# MainBoard_V1_2.net
KiCad netlist of a schematic drawn in EAGLE
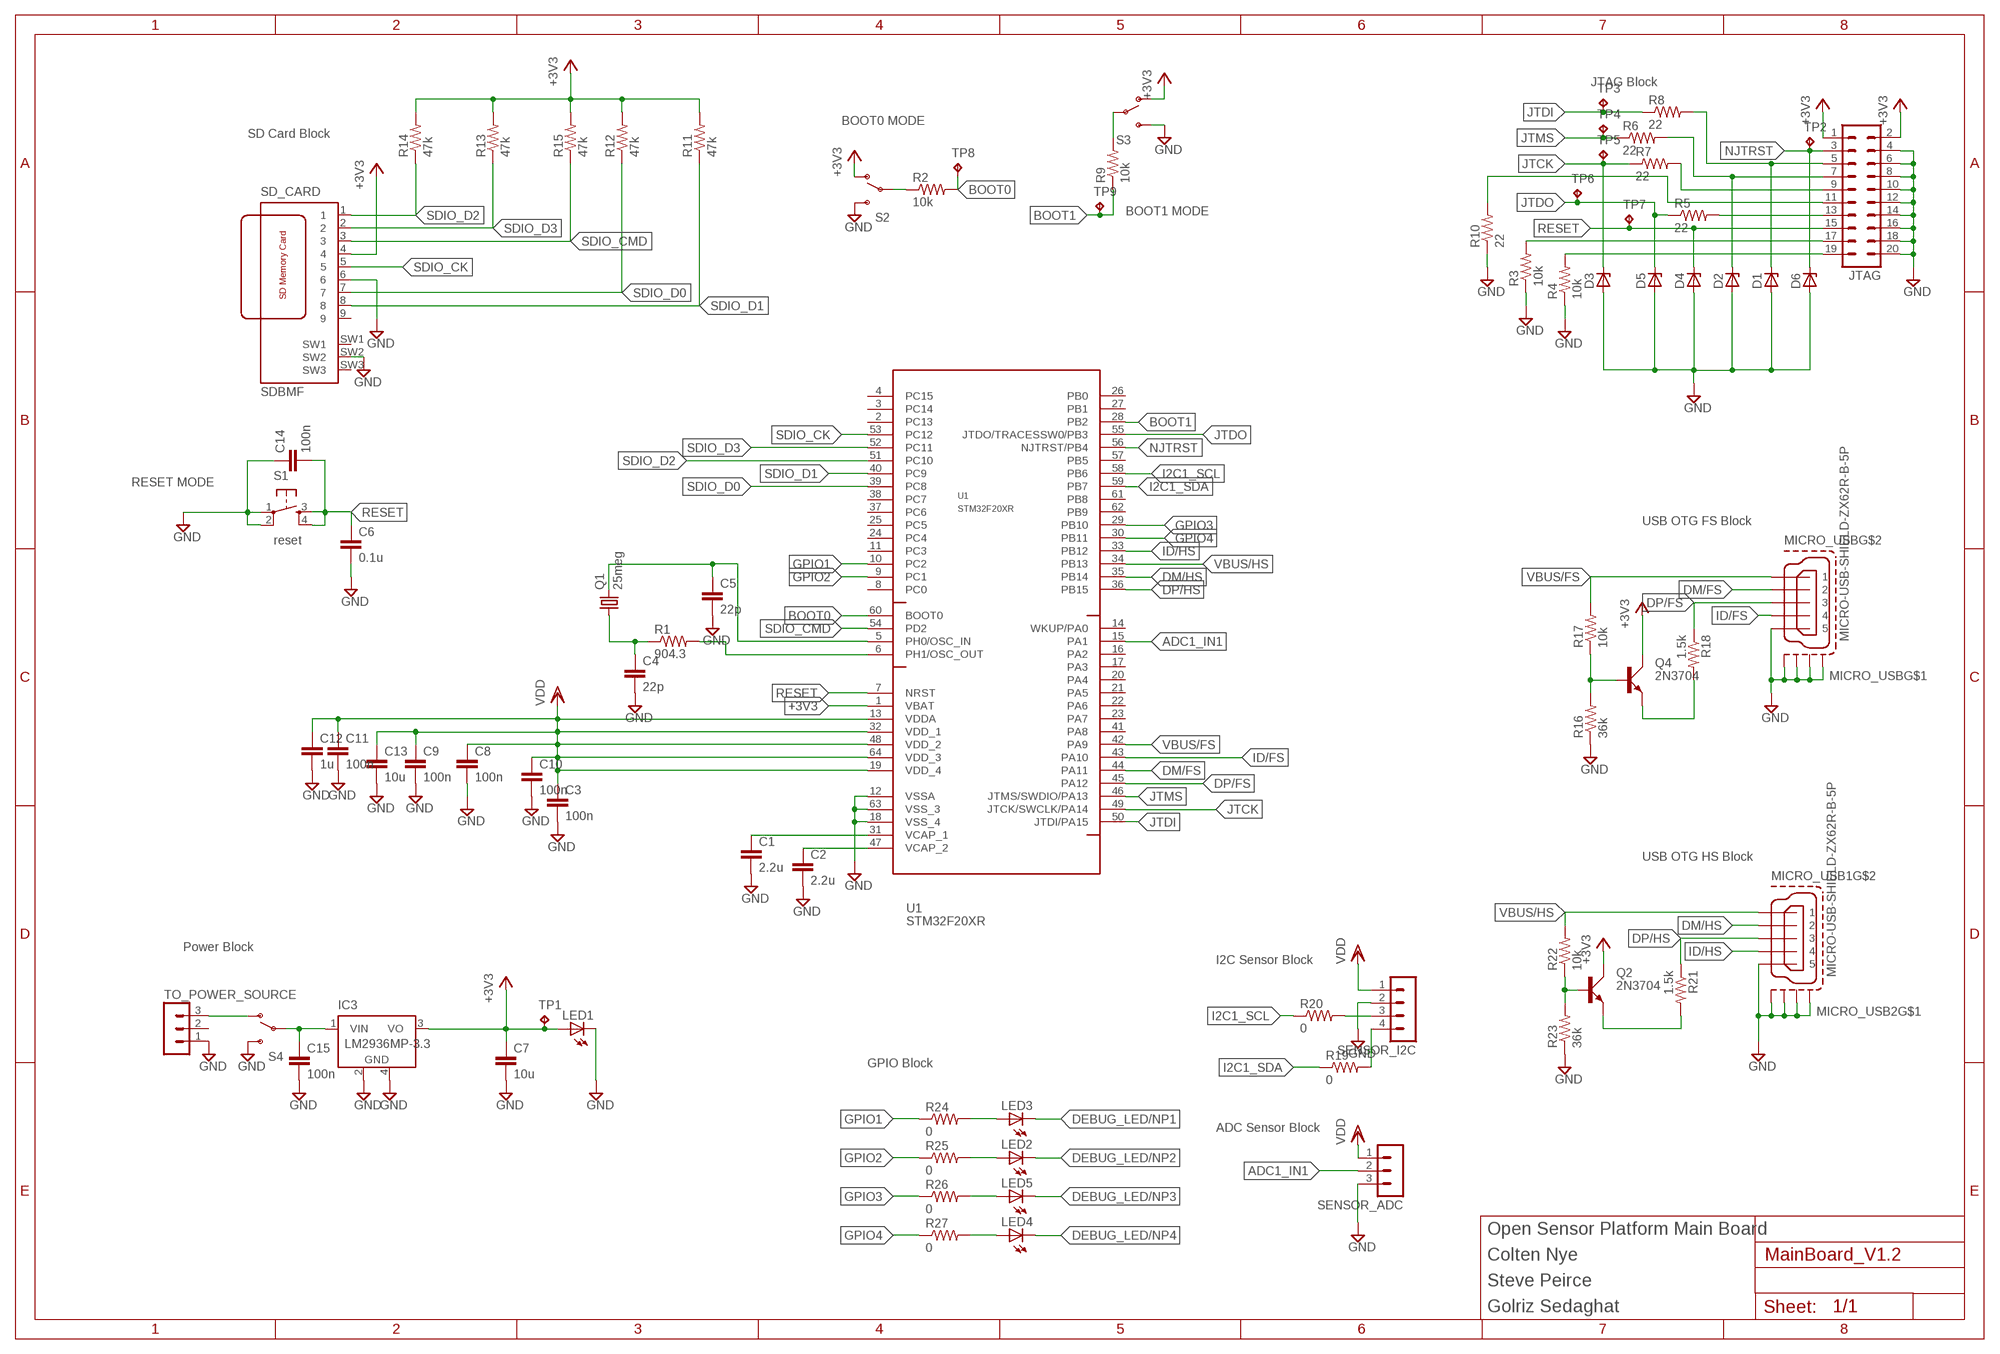
[diagram p0: schematic, sheet 1]

(export (version "E")
  (design (tool "Eeschema 10.0.6"))
  (components
    (comp (ref "C1")
      (value "2.2u")
      (footprint "eagle-import:C0805")
      (libsource (lib "eagle-import") (part "C-EUC0805"))
    )
    (comp (ref "C2")
      (value "2.2u")
      (footprint "eagle-import:C0805")
      (libsource (lib "eagle-import") (part "C-EUC0805"))
    )
    (comp (ref "C3")
      (value "100n")
      (footprint "eagle-import:C0805")
      (libsource (lib "eagle-import") (part "C-EUC0805"))
    )
    (comp (ref "C4")
      (value "22p")
      (footprint "eagle-import:C0805")
      (libsource (lib "eagle-import") (part "C-EUC0805"))
    )
    (comp (ref "C5")
      (value "22p")
      (footprint "eagle-import:C0805")
      (libsource (lib "eagle-import") (part "C-EUC0805"))
    )
    (comp (ref "C6")
      (value "0.1u")
      (footprint "eagle-import:C0805")
      (libsource (lib "eagle-import") (part "C-EUC0805"))
    )
    (comp (ref "C7")
      (value "10u")
      (footprint "eagle-import:C0805")
      (libsource (lib "eagle-import") (part "C-EUC0805"))
    )
    (comp (ref "C8")
      (value "100n")
      (footprint "eagle-import:C0805")
      (libsource (lib "eagle-import") (part "C-EUC0805"))
    )
    (comp (ref "C9")
      (value "100n")
      (footprint "eagle-import:C0805")
      (libsource (lib "eagle-import") (part "C-EUC0805"))
    )
    (comp (ref "C10")
      (value "100n")
      (footprint "eagle-import:C0805")
      (libsource (lib "eagle-import") (part "C-EUC0805"))
    )
    (comp (ref "C11")
      (value "100n")
      (footprint "eagle-import:C0805")
      (libsource (lib "eagle-import") (part "C-EUC0805"))
    )
    (comp (ref "C12")
      (value "1u")
      (footprint "eagle-import:C0805")
      (libsource (lib "eagle-import") (part "C-EUC0805"))
    )
    (comp (ref "C13")
      (value "10u")
      (footprint "eagle-import:C0805")
      (libsource (lib "eagle-import") (part "C-EUC0805"))
    )
    (comp (ref "C14")
      (value "100n")
      (footprint "eagle-import:C0805")
      (libsource (lib "eagle-import") (part "C-EUC0805"))
    )
    (comp (ref "C15")
      (value "100n")
      (footprint "eagle-import:C0805")
      (libsource (lib "eagle-import") (part "C-EUC0805"))
    )
    (comp (ref "D1")
      (value "ZENER-DIODEZD-5")
      (footprint "eagle-import:ZDIO-5")
      (libsource (lib "eagle-import") (part "ZENER-DIODEZD-5"))
    )
    (comp (ref "D2")
      (value "ZENER-DIODEZD-5")
      (footprint "eagle-import:ZDIO-5")
      (libsource (lib "eagle-import") (part "ZENER-DIODEZD-5"))
    )
    (comp (ref "D3")
      (value "ZENER-DIODEZD-5")
      (footprint "eagle-import:ZDIO-5")
      (libsource (lib "eagle-import") (part "ZENER-DIODEZD-5"))
    )
    (comp (ref "D4")
      (value "ZENER-DIODEZD-5")
      (footprint "eagle-import:ZDIO-5")
      (libsource (lib "eagle-import") (part "ZENER-DIODEZD-5"))
    )
    (comp (ref "D5")
      (value "ZENER-DIODEZD-5")
      (footprint "eagle-import:ZDIO-5")
      (libsource (lib "eagle-import") (part "ZENER-DIODEZD-5"))
    )
    (comp (ref "D6")
      (value "ZENER-DIODEZD-5")
      (footprint "eagle-import:ZDIO-5")
      (libsource (lib "eagle-import") (part "ZENER-DIODEZD-5"))
    )
    (comp (ref "IC3")
      (value "LM2936MP-3.3")
      (footprint "eagle-import:SOT223")
      (fields (field (name "MF") "NATIONAL SEMICONDUCTOR") (field (name "MPN") "LM2936MP-3.3/NOPB"))
      (libsource (lib "eagle-import") (part "LM2936MP?-3.3"))
    )
    (comp (ref "JTAG")
      (value "MA10-2")
      (footprint "eagle-import:MA10-2")
      (libsource (lib "eagle-import") (part "MA10-2"))
    )
    (comp (ref "LED1")
      (value "LEDSML0805")
      (footprint "eagle-import:SML0805")
      (libsource (lib "eagle-import") (part "LEDSML0805"))
    )
    (comp (ref "LED2")
      (value "LEDSML0805")
      (footprint "eagle-import:SML0805")
      (libsource (lib "eagle-import") (part "LEDSML0805"))
    )
    (comp (ref "LED3")
      (value "LEDSML0805")
      (footprint "eagle-import:SML0805")
      (libsource (lib "eagle-import") (part "LEDSML0805"))
    )
    (comp (ref "LED4")
      (value "LEDSML0805")
      (footprint "eagle-import:SML0805")
      (libsource (lib "eagle-import") (part "LEDSML0805"))
    )
    (comp (ref "LED5")
      (value "LEDSML0805")
      (footprint "eagle-import:SML0805")
      (libsource (lib "eagle-import") (part "LEDSML0805"))
    )
    (comp (ref "MICRO_USB")
      (value "MICRO-USB-SHIELD-ZX62R-B-5P")
      (footprint "eagle-import:ZX62R-B-5P")
      (libsource (lib "eagle-import") (part "MICRO-USB-SHIELD-ZX62R-B-5P"))
    )
    (comp (ref "MICRO_USB1")
      (value "MICRO-USB-SHIELD-ZX62R-B-5P")
      (footprint "eagle-import:ZX62R-B-5P")
      (libsource (lib "eagle-import") (part "MICRO-USB-SHIELD-ZX62R-B-5P"))
    )
    (comp (ref "MICRO_USB2")
      (value "MICRO-USB-SHIELD-ZX62R-B-5P")
      (footprint "eagle-import:ZX62R-B-5P")
      (libsource (lib "eagle-import") (part "MICRO-USB-SHIELD-ZX62R-B-5P"))
    )
    (comp (ref "Q1")
      (value "25meg")
      (footprint "eagle-import:HC49_S")
      (libsource (lib "eagle-import") (part "CRYSTALHC49S"))
    )
    (comp (ref "Q2")
      (value "2N3704")
      (footprint "eagle-import:TO92C")
      (libsource (lib "eagle-import") (part "2N3704"))
    )
    (comp (ref "Q4")
      (value "2N3704")
      (footprint "eagle-import:TO92C")
      (libsource (lib "eagle-import") (part "2N3704"))
    )
    (comp (ref "R1")
      (value "904.3")
      (footprint "eagle-import:R0805")
      (libsource (lib "eagle-import") (part "R-US_R0805"))
    )
    (comp (ref "R2")
      (value "10k")
      (footprint "eagle-import:R0805")
      (libsource (lib "eagle-import") (part "R-US_R0805"))
    )
    (comp (ref "R3")
      (value "10k")
      (footprint "eagle-import:R0805")
      (libsource (lib "eagle-import") (part "R-US_R0805"))
    )
    (comp (ref "R4")
      (value "10k")
      (footprint "eagle-import:R0805")
      (libsource (lib "eagle-import") (part "R-US_R0805"))
    )
    (comp (ref "R5")
      (value "22")
      (footprint "eagle-import:R0805")
      (libsource (lib "eagle-import") (part "R-US_R0805"))
    )
    (comp (ref "R6")
      (value "22")
      (footprint "eagle-import:R0805")
      (libsource (lib "eagle-import") (part "R-US_R0805"))
    )
    (comp (ref "R7")
      (value "22")
      (footprint "eagle-import:R0805")
      (libsource (lib "eagle-import") (part "R-US_R0805"))
    )
    (comp (ref "R8")
      (value "22")
      (footprint "eagle-import:R0805")
      (libsource (lib "eagle-import") (part "R-US_R0805"))
    )
    (comp (ref "R9")
      (value "10k")
      (footprint "eagle-import:R0805")
      (libsource (lib "eagle-import") (part "R-US_R0805"))
    )
    (comp (ref "R10")
      (value "22")
      (footprint "eagle-import:R0805")
      (libsource (lib "eagle-import") (part "R-US_R0805"))
    )
    (comp (ref "R11")
      (value "47k")
      (footprint "eagle-import:R0805")
      (libsource (lib "eagle-import") (part "R-US_R0805"))
    )
    (comp (ref "R12")
      (value "47k")
      (footprint "eagle-import:R0805")
      (libsource (lib "eagle-import") (part "R-US_R0805"))
    )
    (comp (ref "R13")
      (value "47k")
      (footprint "eagle-import:R0805")
      (libsource (lib "eagle-import") (part "R-US_R0805"))
    )
    (comp (ref "R14")
      (value "47k")
      (footprint "eagle-import:R0805")
      (libsource (lib "eagle-import") (part "R-US_R0805"))
    )
    (comp (ref "R15")
      (value "47k")
      (footprint "eagle-import:R0805")
      (libsource (lib "eagle-import") (part "R-US_R0805"))
    )
    (comp (ref "R16")
      (value "36k")
      (footprint "eagle-import:R0805")
      (libsource (lib "eagle-import") (part "R-US_R0805"))
    )
    (comp (ref "R17")
      (value "10k")
      (footprint "eagle-import:R0805")
      (libsource (lib "eagle-import") (part "R-US_R0805"))
    )
    (comp (ref "R18")
      (value "1.5k")
      (footprint "eagle-import:R0805")
      (libsource (lib "eagle-import") (part "R-US_R0805"))
    )
    (comp (ref "R19")
      (value "0")
      (footprint "eagle-import:R0805")
      (libsource (lib "eagle-import") (part "R-US_R0805"))
    )
    (comp (ref "R20")
      (value "0")
      (footprint "eagle-import:R0805")
      (libsource (lib "eagle-import") (part "R-US_R0805"))
    )
    (comp (ref "R21")
      (value "1.5k")
      (footprint "eagle-import:R0805")
      (libsource (lib "eagle-import") (part "R-US_R0805"))
    )
    (comp (ref "R22")
      (value "10k")
      (footprint "eagle-import:R0805")
      (libsource (lib "eagle-import") (part "R-US_R0805"))
    )
    (comp (ref "R23")
      (value "36k")
      (footprint "eagle-import:R0805")
      (libsource (lib "eagle-import") (part "R-US_R0805"))
    )
    (comp (ref "R24")
      (value "0")
      (footprint "eagle-import:R0805")
      (libsource (lib "eagle-import") (part "R-US_R0805"))
    )
    (comp (ref "R25")
      (value "0")
      (footprint "eagle-import:R0805")
      (libsource (lib "eagle-import") (part "R-US_R0805"))
    )
    (comp (ref "R26")
      (value "0")
      (footprint "eagle-import:R0805")
      (libsource (lib "eagle-import") (part "R-US_R0805"))
    )
    (comp (ref "R27")
      (value "0")
      (footprint "eagle-import:R0805")
      (libsource (lib "eagle-import") (part "R-US_R0805"))
    )
    (comp (ref "S1")
      (value "reset")
      (footprint "eagle-import:TACTILE-SWITCH-SMD")
      (libsource (lib "eagle-import") (part "TAC_SWITCHSMD"))
    )
    (comp (ref "S2")
      (value "SWITCH-SPDT-SMD-A")
      (footprint "eagle-import:SWITCH-SPST-SMD-A")
      (libsource (lib "eagle-import") (part "SWITCH-SPDT-SMD-A"))
    )
    (comp (ref "S3")
      (value "SWITCH-SPDT-SMD-A")
      (footprint "eagle-import:SWITCH-SPST-SMD-A")
      (libsource (lib "eagle-import") (part "SWITCH-SPDT-SMD-A"))
    )
    (comp (ref "S4")
      (value "SWITCH-SPDT-SMD-A")
      (footprint "eagle-import:SWITCH-SPST-SMD-A")
      (libsource (lib "eagle-import") (part "SWITCH-SPDT-SMD-A"))
    )
    (comp (ref "SD_CARD")
      (value "SDBMF")
      (footprint "eagle-import:SDBMF-009XXBXX2")
      (libsource (lib "eagle-import") (part "SDBMF"))
    )
    (comp (ref "SENSOR_ADC")
      (value "MA03-1")
      (footprint "eagle-import:MA03-1")
      (libsource (lib "eagle-import") (part "MA03-1"))
    )
    (comp (ref "SENSOR_I2C")
      (value "MA04-1")
      (footprint "eagle-import:MA04-1")
      (libsource (lib "eagle-import") (part "MA04-1"))
    )
    (comp (ref "TO_POWER_SOURCE")
      (value "MA03-1")
      (footprint "eagle-import:MA03-1")
      (libsource (lib "eagle-import") (part "MA03-1"))
    )
    (comp (ref "TP1")
      (value "TPB1,27")
      (footprint "eagle-import:B1,27")
      (libsource (lib "eagle-import") (part "TPB1,27"))
    )
    (comp (ref "TP2")
      (value "TPB1,27")
      (footprint "eagle-import:B1,27")
      (libsource (lib "eagle-import") (part "TPB1,27"))
    )
    (comp (ref "TP3")
      (value "TPB1,27")
      (footprint "eagle-import:B1,27")
      (libsource (lib "eagle-import") (part "TPB1,27"))
    )
    (comp (ref "TP4")
      (value "TPB1,27")
      (footprint "eagle-import:B1,27")
      (libsource (lib "eagle-import") (part "TPB1,27"))
    )
    (comp (ref "TP5")
      (value "TPB1,27")
      (footprint "eagle-import:B1,27")
      (libsource (lib "eagle-import") (part "TPB1,27"))
    )
    (comp (ref "TP6")
      (value "TPB1,27")
      (footprint "eagle-import:B1,27")
      (libsource (lib "eagle-import") (part "TPB1,27"))
    )
    (comp (ref "TP7")
      (value "TPB1,27")
      (footprint "eagle-import:B1,27")
      (libsource (lib "eagle-import") (part "TPB1,27"))
    )
    (comp (ref "TP8")
      (value "TPB1,27")
      (footprint "eagle-import:B1,27")
      (libsource (lib "eagle-import") (part "TPB1,27"))
    )
    (comp (ref "TP9")
      (value "TPB1,27")
      (footprint "eagle-import:B1,27")
      (libsource (lib "eagle-import") (part "TPB1,27"))
    )
    (comp (ref "U1")
      (value "STM32F20XR")
      (footprint "eagle-import:LQFP64")
      (libsource (lib "eagle-import") (part "STM32F20XR"))
    )
  )
  (nets
    (net (code "1") (name "+3V3") (class "Default")
      (node (ref "C7") (pin "1") (pinfunction "1_1") (pintype "passive"))
      (node (ref "IC3") (pin "3") (pinfunction "VO_3") (pintype "passive"))
      (node (ref "JTAG") (pin "1") (pinfunction "1_1") (pintype "passive"))
      (node (ref "JTAG") (pin "2") (pinfunction "2_2") (pintype "passive"))
      (node (ref "LED1") (pin "A") (pinfunction "A_A") (pintype "passive"))
      (node (ref "Q2") (pin "C") (pinfunction "C_C") (pintype "passive"))
      (node (ref "Q4") (pin "C") (pinfunction "C_C") (pintype "passive"))
      (node (ref "R11") (pin "2") (pinfunction "2_2") (pintype "passive"))
      (node (ref "R12") (pin "2") (pinfunction "2_2") (pintype "passive"))
      (node (ref "R13") (pin "2") (pinfunction "2_2") (pintype "passive"))
      (node (ref "R14") (pin "2") (pinfunction "2_2") (pintype "passive"))
      (node (ref "R15") (pin "2") (pinfunction "2_2") (pintype "passive"))
      (node (ref "S2") (pin "1") (pinfunction "O_1") (pintype "passive"))
      (node (ref "S3") (pin "1") (pinfunction "O_1") (pintype "passive"))
      (node (ref "SD_CARD") (pin "4") (pinfunction "4_4") (pintype "passive"))
      (node (ref "TP1") (pin "TP") (pinfunction "TP_TP") (pintype "input"))
      (node (ref "U1") (pin "1") (pinfunction "VBAT_1") (pintype "power_in"))
    )
    (net (code "2") (name "ADC1_IN1") (class "Default")
      (node (ref "SENSOR_ADC") (pin "2") (pinfunction "2_2") (pintype "passive"))
      (node (ref "U1") (pin "15") (pinfunction "PA1_15") (pintype "bidirectional"))
    )
    (net (code "3") (name "BOOT0") (class "Default")
      (node (ref "R2") (pin "2") (pinfunction "2_2") (pintype "passive"))
      (node (ref "TP8") (pin "TP") (pinfunction "TP_TP") (pintype "input"))
      (node (ref "U1") (pin "60") (pinfunction "BOOT0_60") (pintype "bidirectional"))
    )
    (net (code "4") (name "BOOT1") (class "Default")
      (node (ref "R9") (pin "1") (pinfunction "1_1") (pintype "passive"))
      (node (ref "TP9") (pin "TP") (pinfunction "TP_TP") (pintype "input"))
      (node (ref "U1") (pin "28") (pinfunction "PB2_28") (pintype "bidirectional"))
    )
    (net (code "5") (name "DEBUG_LED{slash}NP1") (class "Default")
      (node (ref "LED3") (pin "C") (pinfunction "C_C") (pintype "passive"))
    )
    (net (code "6") (name "DEBUG_LED{slash}NP2") (class "Default")
      (node (ref "LED2") (pin "C") (pinfunction "C_C") (pintype "passive"))
    )
    (net (code "7") (name "DEBUG_LED{slash}NP3") (class "Default")
      (node (ref "LED5") (pin "C") (pinfunction "C_C") (pintype "passive"))
    )
    (net (code "8") (name "DEBUG_LED{slash}NP4") (class "Default")
      (node (ref "LED4") (pin "C") (pinfunction "C_C") (pintype "passive"))
    )
    (net (code "9") (name "DM{slash}FS") (class "Default")
      (node (ref "MICRO_USB") (pin "2") (pinfunction "2_2") (pintype "input"))
      (node (ref "U1") (pin "44") (pinfunction "PA11_44") (pintype "bidirectional"))
    )
    (net (code "10") (name "DM{slash}HS") (class "Default")
      (node (ref "MICRO_USB1") (pin "2") (pinfunction "2_2") (pintype "input"))
      (node (ref "U1") (pin "35") (pinfunction "PB14_35") (pintype "bidirectional"))
    )
    (net (code "11") (name "DP{slash}FS") (class "Default")
      (node (ref "MICRO_USB") (pin "3") (pinfunction "3_3") (pintype "input"))
      (node (ref "R18") (pin "1") (pinfunction "1_1") (pintype "passive"))
      (node (ref "U1") (pin "45") (pinfunction "PA12_45") (pintype "bidirectional"))
    )
    (net (code "12") (name "DP{slash}HS") (class "Default")
      (node (ref "MICRO_USB1") (pin "3") (pinfunction "3_3") (pintype "input"))
      (node (ref "R21") (pin "1") (pinfunction "1_1") (pintype "passive"))
      (node (ref "U1") (pin "36") (pinfunction "PB15_36") (pintype "bidirectional"))
    )
    (net (code "13") (name "GND") (class "Default")
      (node (ref "C1") (pin "2") (pinfunction "2_2") (pintype "passive"))
      (node (ref "C10") (pin "2") (pinfunction "2_2") (pintype "passive"))
      (node (ref "C11") (pin "2") (pinfunction "2_2") (pintype "passive"))
      (node (ref "C12") (pin "2") (pinfunction "2_2") (pintype "passive"))
      (node (ref "C13") (pin "2") (pinfunction "2_2") (pintype "passive"))
      (node (ref "C14") (pin "1") (pinfunction "1_1") (pintype "passive"))
      (node (ref "C15") (pin "2") (pinfunction "2_2") (pintype "passive"))
      (node (ref "C2") (pin "2") (pinfunction "2_2") (pintype "passive"))
      (node (ref "C3") (pin "2") (pinfunction "2_2") (pintype "passive"))
      (node (ref "C4") (pin "2") (pinfunction "2_2") (pintype "passive"))
      (node (ref "C5") (pin "2") (pinfunction "2_2") (pintype "passive"))
      (node (ref "C6") (pin "2") (pinfunction "2_2") (pintype "passive"))
      (node (ref "C7") (pin "2") (pinfunction "2_2") (pintype "passive"))
      (node (ref "C8") (pin "2") (pinfunction "2_2") (pintype "passive"))
      (node (ref "C9") (pin "2") (pinfunction "2_2") (pintype "passive"))
      (node (ref "D1") (pin "A") (pinfunction "A_A") (pintype "passive"))
      (node (ref "D2") (pin "A") (pinfunction "A_A") (pintype "passive"))
      (node (ref "D3") (pin "A") (pinfunction "A_A") (pintype "passive"))
      (node (ref "D4") (pin "A") (pinfunction "A_A") (pintype "passive"))
      (node (ref "D5") (pin "A") (pinfunction "A_A") (pintype "passive"))
      (node (ref "D6") (pin "A") (pinfunction "A_A") (pintype "passive"))
      (node (ref "IC3") (pin "2") (pinfunction "GND_2") (pintype "passive"))
      (node (ref "IC3") (pin "4") (pinfunction "GND_4") (pintype "passive"))
      (node (ref "JTAG") (pin "10") (pinfunction "10_10") (pintype "passive"))
      (node (ref "JTAG") (pin "12") (pinfunction "12_12") (pintype "passive"))
      (node (ref "JTAG") (pin "14") (pinfunction "14_14") (pintype "passive"))
      (node (ref "JTAG") (pin "16") (pinfunction "16_16") (pintype "passive"))
      (node (ref "JTAG") (pin "18") (pinfunction "18_18") (pintype "passive"))
      (node (ref "JTAG") (pin "20") (pinfunction "20_20") (pintype "passive"))
      (node (ref "JTAG") (pin "4") (pinfunction "4_4") (pintype "passive"))
      (node (ref "JTAG") (pin "6") (pinfunction "6_6") (pintype "passive"))
      (node (ref "JTAG") (pin "8") (pinfunction "8_8") (pintype "passive"))
      (node (ref "LED1") (pin "C") (pinfunction "C_C") (pintype "passive"))
      (node (ref "MICRO_USB") (pin "5") (pinfunction "5_5") (pintype "input"))
      (node (ref "MICRO_USB") (pin "M1") (pinfunction "S1_M1") (pintype "passive"))
      (node (ref "MICRO_USB") (pin "M2") (pinfunction "S2_M2") (pintype "passive"))
      (node (ref "MICRO_USB") (pin "M3") (pinfunction "S3_M3") (pintype "passive"))
      (node (ref "MICRO_USB") (pin "M4") (pinfunction "S4_M4") (pintype "passive"))
      (node (ref "MICRO_USB1") (pin "5") (pinfunction "5_5") (pintype "input"))
      (node (ref "MICRO_USB2") (pin "M1") (pinfunction "S1_M1") (pintype "passive"))
      (node (ref "MICRO_USB2") (pin "M2") (pinfunction "S2_M2") (pintype "passive"))
      (node (ref "MICRO_USB2") (pin "M3") (pinfunction "S3_M3") (pintype "passive"))
      (node (ref "MICRO_USB2") (pin "M4") (pinfunction "S4_M4") (pintype "passive"))
      (node (ref "R10") (pin "1") (pinfunction "1_1") (pintype "passive"))
      (node (ref "R16") (pin "1") (pinfunction "1_1") (pintype "passive"))
      (node (ref "R23") (pin "1") (pinfunction "1_1") (pintype "passive"))
      (node (ref "R3") (pin "1") (pinfunction "1_1") (pintype "passive"))
      (node (ref "R4") (pin "1") (pinfunction "1_1") (pintype "passive"))
      (node (ref "S1") (pin "1") (pinfunction "1_1") (pintype "passive"))
      (node (ref "S1") (pin "2") (pinfunction "2_2") (pintype "passive"))
      (node (ref "S2") (pin "3") (pinfunction "S_3") (pintype "passive"))
      (node (ref "S3") (pin "3") (pinfunction "S_3") (pintype "passive"))
      (node (ref "S4") (pin "3") (pinfunction "S_3") (pintype "passive"))
      (node (ref "SD_CARD") (pin "6") (pinfunction "6_6") (pintype "passive"))
      (node (ref "SD_CARD") (pin "SW2") (pinfunction "SW2_SW2") (pintype "passive"))
      (node (ref "SENSOR_ADC") (pin "3") (pinfunction "3_3") (pintype "passive"))
      (node (ref "SENSOR_I2C") (pin "2") (pinfunction "2_2") (pintype "passive"))
      (node (ref "TO_POWER_SOURCE") (pin "1") (pinfunction "1_1") (pintype "passive"))
      (node (ref "U1") (pin "12") (pinfunction "VSSA_12") (pintype "power_in"))
      (node (ref "U1") (pin "18") (pinfunction "VSS_4_18") (pintype "power_in"))
      (node (ref "U1") (pin "63") (pinfunction "VSS_3_63") (pintype "power_in"))
    )
    (net (code "14") (name "GPIO1") (class "Default")
      (node (ref "R24") (pin "1") (pinfunction "1_1") (pintype "passive"))
      (node (ref "U1") (pin "10") (pinfunction "PC2_10") (pintype "bidirectional"))
    )
    (net (code "15") (name "GPIO2") (class "Default")
      (node (ref "R25") (pin "1") (pinfunction "1_1") (pintype "passive"))
      (node (ref "U1") (pin "9") (pinfunction "PC1_9") (pintype "bidirectional"))
    )
    (net (code "16") (name "GPIO3") (class "Default")
      (node (ref "R26") (pin "1") (pinfunction "1_1") (pintype "passive"))
      (node (ref "U1") (pin "29") (pinfunction "PB10_29") (pintype "bidirectional"))
    )
    (net (code "17") (name "GPIO4") (class "Default")
      (node (ref "R27") (pin "1") (pinfunction "1_1") (pintype "passive"))
      (node (ref "U1") (pin "30") (pinfunction "PB11_30") (pintype "bidirectional"))
    )
    (net (code "18") (name "I2C1_SCL") (class "Default")
      (node (ref "R20") (pin "1") (pinfunction "1_1") (pintype "passive"))
      (node (ref "U1") (pin "58") (pinfunction "PB6_58") (pintype "bidirectional"))
    )
    (net (code "19") (name "I2C1_SDA") (class "Default")
      (node (ref "R19") (pin "1") (pinfunction "1_1") (pintype "passive"))
      (node (ref "U1") (pin "59") (pinfunction "PB7_59") (pintype "bidirectional"))
    )
    (net (code "20") (name "ID{slash}FS") (class "Default")
      (node (ref "MICRO_USB") (pin "4") (pinfunction "4_4") (pintype "input"))
      (node (ref "U1") (pin "43") (pinfunction "PA10_43") (pintype "bidirectional"))
    )
    (net (code "21") (name "ID{slash}HS") (class "Default")
      (node (ref "MICRO_USB1") (pin "4") (pinfunction "4_4") (pintype "input"))
      (node (ref "U1") (pin "33") (pinfunction "PB12_33") (pintype "bidirectional"))
    )
    (net (code "22") (name "JTCK") (class "Default")
      (node (ref "D3") (pin "C") (pinfunction "C_C") (pintype "passive"))
      (node (ref "R7") (pin "1") (pinfunction "1_1") (pintype "passive"))
      (node (ref "TP5") (pin "TP") (pinfunction "TP_TP") (pintype "input"))
      (node (ref "U1") (pin "49") (pinfunction "JTCK/SWCLK/PA14_49") (pintype "bidirectional"))
    )
    (net (code "23") (name "JTDI") (class "Default")
      (node (ref "R8") (pin "1") (pinfunction "1_1") (pintype "passive"))
      (node (ref "TP3") (pin "TP") (pinfunction "TP_TP") (pintype "input"))
      (node (ref "U1") (pin "50") (pinfunction "JTDI/PA15_50") (pintype "bidirectional"))
    )
    (net (code "24") (name "JTDO") (class "Default")
      (node (ref "D5") (pin "C") (pinfunction "C_C") (pintype "passive"))
      (node (ref "R5") (pin "1") (pinfunction "1_1") (pintype "passive"))
      (node (ref "TP6") (pin "TP") (pinfunction "TP_TP") (pintype "input"))
      (node (ref "U1") (pin "55") (pinfunction "JTDO/TRACESSW0/PB3_55") (pintype "bidirectional"))
    )
    (net (code "25") (name "JTMS") (class "Default")
      (node (ref "R6") (pin "1") (pinfunction "1_1") (pintype "passive"))
      (node (ref "TP4") (pin "TP") (pinfunction "TP_TP") (pintype "input"))
      (node (ref "U1") (pin "46") (pinfunction "JTMS/SWDIO/PA13_46") (pintype "bidirectional"))
    )
    (net (code "26") (name "NJTRST") (class "Default")
      (node (ref "D6") (pin "C") (pinfunction "C_C") (pintype "passive"))
      (node (ref "JTAG") (pin "3") (pinfunction "3_3") (pintype "passive"))
      (node (ref "TP2") (pin "TP") (pinfunction "TP_TP") (pintype "input"))
      (node (ref "U1") (pin "56") (pinfunction "NJTRST/PB4_56") (pintype "bidirectional"))
    )
    (net (code "27") (name "Net-(C4-Pad1)") (class "Default")
      (node (ref "C4") (pin "1") (pinfunction "1_1") (pintype "passive"))
      (node (ref "Q1") (pin "1") (pinfunction "1_1") (pintype "passive"))
      (node (ref "R1") (pin "1") (pinfunction "1_1") (pintype "passive"))
    )
    (net (code "28") (name "Net-(D1-PadC)") (class "Default")
      (node (ref "D1") (pin "C") (pinfunction "C_C") (pintype "passive"))
      (node (ref "JTAG") (pin "5") (pinfunction "5_5") (pintype "passive"))
      (node (ref "R8") (pin "2") (pinfunction "2_2") (pintype "passive"))
    )
    (net (code "29") (name "Net-(D2-PadC)") (class "Default")
      (node (ref "D2") (pin "C") (pinfunction "C_C") (pintype "passive"))
      (node (ref "JTAG") (pin "7") (pinfunction "7_7") (pintype "passive"))
      (node (ref "R6") (pin "2") (pinfunction "2_2") (pintype "passive"))
    )
    (net (code "30") (name "Net-(IC3-VIN)") (class "Default")
      (node (ref "C15") (pin "1") (pinfunction "1_1") (pintype "passive"))
      (node (ref "IC3") (pin "1") (pinfunction "VIN_1") (pintype "input"))
      (node (ref "S4") (pin "2") (pinfunction "P_2") (pintype "passive"))
    )
    (net (code "31") (name "Net-(JTAG-Pad9)") (class "Default")
      (node (ref "JTAG") (pin "9") (pinfunction "9_9") (pintype "passive"))
      (node (ref "R7") (pin "2") (pinfunction "2_2") (pintype "passive"))
    )
    (net (code "32") (name "Net-(JTAG-Pad11)") (class "Default")
      (node (ref "JTAG") (pin "11") (pinfunction "11_11") (pintype "passive"))
      (node (ref "R10") (pin "2") (pinfunction "2_2") (pintype "passive"))
    )
    (net (code "33") (name "Net-(JTAG-Pad13)") (class "Default")
      (node (ref "JTAG") (pin "13") (pinfunction "13_13") (pintype "passive"))
      (node (ref "R5") (pin "2") (pinfunction "2_2") (pintype "passive"))
    )
    (net (code "34") (name "Net-(JTAG-Pad17)") (class "Default")
      (node (ref "JTAG") (pin "17") (pinfunction "17_17") (pintype "passive"))
      (node (ref "R3") (pin "2") (pinfunction "2_2") (pintype "passive"))
    )
    (net (code "35") (name "Net-(JTAG-Pad19)") (class "Default")
      (node (ref "JTAG") (pin "19") (pinfunction "19_19") (pintype "passive"))
      (node (ref "R4") (pin "2") (pinfunction "2_2") (pintype "passive"))
    )
    (net (code "36") (name "Net-(LED2-PadA)") (class "Default")
      (node (ref "LED2") (pin "A") (pinfunction "A_A") (pintype "passive"))
      (node (ref "R25") (pin "2") (pinfunction "2_2") (pintype "passive"))
    )
    (net (code "37") (name "Net-(LED3-PadA)") (class "Default")
      (node (ref "LED3") (pin "A") (pinfunction "A_A") (pintype "passive"))
      (node (ref "R24") (pin "2") (pinfunction "2_2") (pintype "passive"))
    )
    (net (code "38") (name "Net-(LED4-PadA)") (class "Default")
      (node (ref "LED4") (pin "A") (pinfunction "A_A") (pintype "passive"))
      (node (ref "R27") (pin "2") (pinfunction "2_2") (pintype "passive"))
    )
    (net (code "39") (name "Net-(LED5-PadA)") (class "Default")
      (node (ref "LED5") (pin "A") (pinfunction "A_A") (pintype "passive"))
      (node (ref "R26") (pin "2") (pinfunction "2_2") (pintype "passive"))
    )
    (net (code "40") (name "Net-(Q2-PadB)") (class "Default")
      (node (ref "Q2") (pin "B") (pinfunction "B_B") (pintype "passive"))
      (node (ref "R22") (pin "1") (pinfunction "1_1") (pintype "passive"))
      (node (ref "R23") (pin "2") (pinfunction "2_2") (pintype "passive"))
    )
    (net (code "41") (name "Net-(Q2-PadE)") (class "Default")
      (node (ref "Q2") (pin "E") (pinfunction "E_E") (pintype "passive"))
      (node (ref "R21") (pin "2") (pinfunction "2_2") (pintype "passive"))
    )
    (net (code "42") (name "Net-(Q4-PadB)") (class "Default")
      (node (ref "Q4") (pin "B") (pinfunction "B_B") (pintype "passive"))
      (node (ref "R16") (pin "2") (pinfunction "2_2") (pintype "passive"))
      (node (ref "R17") (pin "1") (pinfunction "1_1") (pintype "passive"))
    )
    (net (code "43") (name "Net-(Q4-PadE)") (class "Default")
      (node (ref "Q4") (pin "E") (pinfunction "E_E") (pintype "passive"))
      (node (ref "R18") (pin "2") (pinfunction "2_2") (pintype "passive"))
    )
    (net (code "44") (name "Net-(R19-Pad2)") (class "Default")
      (node (ref "R19") (pin "2") (pinfunction "2_2") (pintype "passive"))
      (node (ref "SENSOR_I2C") (pin "4") (pinfunction "4_4") (pintype "passive"))
    )
    (net (code "45") (name "Net-(R20-Pad2)") (class "Default")
      (node (ref "R20") (pin "2") (pinfunction "2_2") (pintype "passive"))
      (node (ref "SENSOR_I2C") (pin "3") (pinfunction "3_3") (pintype "passive"))
    )
    (net (code "46") (name "Net-(S2-P)") (class "Default")
      (node (ref "R2") (pin "1") (pinfunction "1_1") (pintype "passive"))
      (node (ref "S2") (pin "2") (pinfunction "P_2") (pintype "passive"))
    )
    (net (code "47") (name "Net-(S3-P)") (class "Default")
      (node (ref "R9") (pin "2") (pinfunction "2_2") (pintype "passive"))
      (node (ref "S3") (pin "2") (pinfunction "P_2") (pintype "passive"))
    )
    (net (code "48") (name "Net-(S4-O)") (class "Default")
      (node (ref "S4") (pin "1") (pinfunction "O_1") (pintype "passive"))
      (node (ref "TO_POWER_SOURCE") (pin "3") (pinfunction "3_3") (pintype "passive"))
    )
    (net (code "49") (name "Net-(U1-PH0{slash}OSC_IN)") (class "Default")
      (node (ref "C5") (pin "1") (pinfunction "1_1") (pintype "passive"))
      (node (ref "Q1") (pin "2") (pinfunction "2_2") (pintype "passive"))
      (node (ref "U1") (pin "5") (pinfunction "PH0/OSC_IN_5") (pintype "bidirectional"))
    )
    (net (code "50") (name "Net-(U1-PH1{slash}OSC_OUT)") (class "Default")
      (node (ref "R1") (pin "2") (pinfunction "2_2") (pintype "passive"))
      (node (ref "U1") (pin "6") (pinfunction "PH1/OSC_OUT_6") (pintype "bidirectional"))
    )
    (net (code "51") (name "Net-(U1-VCAP_1)") (class "Default")
      (node (ref "C1") (pin "1") (pinfunction "1_1") (pintype "passive"))
      (node (ref "U1") (pin "31") (pinfunction "VCAP_1_31") (pintype "power_in"))
    )
    (net (code "52") (name "Net-(U1-VCAP_2)") (class "Default")
      (node (ref "C2") (pin "1") (pinfunction "1_1") (pintype "passive"))
      (node (ref "U1") (pin "47") (pinfunction "VCAP_2_47") (pintype "power_in"))
    )
    (net (code "53") (name "RESET") (class "Default")
      (node (ref "C14") (pin "2") (pinfunction "2_2") (pintype "passive"))
      (node (ref "C6") (pin "1") (pinfunction "1_1") (pintype "passive"))
      (node (ref "D4") (pin "C") (pinfunction "C_C") (pintype "passive"))
      (node (ref "JTAG") (pin "15") (pinfunction "15_15") (pintype "passive"))
      (node (ref "S1") (pin "3") (pinfunction "3_3") (pintype "passive"))
      (node (ref "S1") (pin "4") (pinfunction "4_4") (pintype "passive"))
      (node (ref "TP7") (pin "TP") (pinfunction "TP_TP") (pintype "input"))
      (node (ref "U1") (pin "7") (pinfunction "NRST_7") (pintype "power_in"))
    )
    (net (code "54") (name "SDIO_CK") (class "Default")
      (node (ref "SD_CARD") (pin "5") (pinfunction "5_5") (pintype "passive"))
      (node (ref "U1") (pin "53") (pinfunction "PC12_53") (pintype "bidirectional"))
    )
    (net (code "55") (name "SDIO_CMD") (class "Default")
      (node (ref "R15") (pin "1") (pinfunction "1_1") (pintype "passive"))
      (node (ref "SD_CARD") (pin "3") (pinfunction "3_3") (pintype "passive"))
      (node (ref "U1") (pin "54") (pinfunction "PD2_54") (pintype "bidirectional"))
    )
    (net (code "56") (name "SDIO_D0") (class "Default")
      (node (ref "R12") (pin "1") (pinfunction "1_1") (pintype "passive"))
      (node (ref "SD_CARD") (pin "7") (pinfunction "7_7") (pintype "passive"))
      (node (ref "U1") (pin "39") (pinfunction "PC8_39") (pintype "bidirectional"))
    )
    (net (code "57") (name "SDIO_D1") (class "Default")
      (node (ref "R11") (pin "1") (pinfunction "1_1") (pintype "passive"))
      (node (ref "SD_CARD") (pin "8") (pinfunction "8_8") (pintype "passive"))
      (node (ref "U1") (pin "40") (pinfunction "PC9_40") (pintype "bidirectional"))
    )
    (net (code "58") (name "SDIO_D2") (class "Default")
      (node (ref "R14") (pin "1") (pinfunction "1_1") (pintype "passive"))
      (node (ref "SD_CARD") (pin "1") (pinfunction "1_1") (pintype "passive"))
      (node (ref "U1") (pin "51") (pinfunction "PC10_51") (pintype "bidirectional"))
    )
    (net (code "59") (name "SDIO_D3") (class "Default")
      (node (ref "R13") (pin "1") (pinfunction "1_1") (pintype "passive"))
      (node (ref "SD_CARD") (pin "2") (pinfunction "2_2") (pintype "passive"))
      (node (ref "U1") (pin "52") (pinfunction "PC11_52") (pintype "bidirectional"))
    )
    (net (code "60") (name "VBUS{slash}FS") (class "Default")
      (node (ref "MICRO_USB") (pin "1") (pinfunction "1_1") (pintype "input"))
      (node (ref "R17") (pin "2") (pinfunction "2_2") (pintype "passive"))
      (node (ref "U1") (pin "42") (pinfunction "PA9_42") (pintype "bidirectional"))
    )
    (net (code "61") (name "VBUS{slash}HS") (class "Default")
      (node (ref "MICRO_USB1") (pin "1") (pinfunction "1_1") (pintype "input"))
      (node (ref "R22") (pin "2") (pinfunction "2_2") (pintype "passive"))
      (node (ref "U1") (pin "34") (pinfunction "PB13_34") (pintype "bidirectional"))
    )
    (net (code "62") (name "VDD") (class "Default")
      (node (ref "C10") (pin "1") (pinfunction "1_1") (pintype "passive"))
      (node (ref "C11") (pin "1") (pinfunction "1_1") (pintype "passive"))
      (node (ref "C12") (pin "1") (pinfunction "1_1") (pintype "passive"))
      (node (ref "C13") (pin "1") (pinfunction "1_1") (pintype "passive"))
      (node (ref "C3") (pin "1") (pinfunction "1_1") (pintype "passive"))
      (node (ref "C8") (pin "1") (pinfunction "1_1") (pintype "passive"))
      (node (ref "C9") (pin "1") (pinfunction "1_1") (pintype "passive"))
      (node (ref "SENSOR_ADC") (pin "1") (pinfunction "1_1") (pintype "passive"))
      (node (ref "SENSOR_I2C") (pin "1") (pinfunction "1_1") (pintype "passive"))
      (node (ref "U1") (pin "13") (pinfunction "VDDA_13") (pintype "power_in"))
      (node (ref "U1") (pin "19") (pinfunction "VDD_4_19") (pintype "power_in"))
      (node (ref "U1") (pin "32") (pinfunction "VDD_1_32") (pintype "power_in"))
      (node (ref "U1") (pin "48") (pinfunction "VDD_2_48") (pintype "power_in"))
      (node (ref "U1") (pin "64") (pinfunction "VDD_3_64") (pintype "power_in"))
    )
    (net (code "63") (name "unconnected-(SD_CARD-Pad9)") (class "Default")
      (node (ref "SD_CARD") (pin "9") (pinfunction "9_9") (pintype "passive"))
    )
    (net (code "64") (name "unconnected-(SD_CARD-PadSW1)") (class "Default")
      (node (ref "SD_CARD") (pin "SW1") (pinfunction "SW1_SW1") (pintype "passive"))
    )
    (net (code "65") (name "unconnected-(SD_CARD-PadSW3)") (class "Default")
      (node (ref "SD_CARD") (pin "SW3") (pinfunction "SW3_SW3") (pintype "passive"))
    )
    (net (code "66") (name "unconnected-(TO_POWER_SOURCE-Pad2)") (class "Default")
      (node (ref "TO_POWER_SOURCE") (pin "2") (pinfunction "2_2") (pintype "passive"))
    )
    (net (code "67") (name "unconnected-(U1-PA2-Pad16)") (class "Default")
      (node (ref "U1") (pin "16") (pinfunction "PA2_16") (pintype "bidirectional"))
    )
    (net (code "68") (name "unconnected-(U1-PA3-Pad17)") (class "Default")
      (node (ref "U1") (pin "17") (pinfunction "PA3_17") (pintype "bidirectional"))
    )
    (net (code "69") (name "unconnected-(U1-PA4-Pad20)") (class "Default")
      (node (ref "U1") (pin "20") (pinfunction "PA4_20") (pintype "bidirectional"))
    )
    (net (code "70") (name "unconnected-(U1-PA5-Pad21)") (class "Default")
      (node (ref "U1") (pin "21") (pinfunction "PA5_21") (pintype "bidirectional"))
    )
    (net (code "71") (name "unconnected-(U1-PA6-Pad22)") (class "Default")
      (node (ref "U1") (pin "22") (pinfunction "PA6_22") (pintype "bidirectional"))
    )
    (net (code "72") (name "unconnected-(U1-PA7-Pad23)") (class "Default")
      (node (ref "U1") (pin "23") (pinfunction "PA7_23") (pintype "bidirectional"))
    )
    (net (code "73") (name "unconnected-(U1-PA8-Pad41)") (class "Default")
      (node (ref "U1") (pin "41") (pinfunction "PA8_41") (pintype "bidirectional"))
    )
    (net (code "74") (name "unconnected-(U1-PB0-Pad26)") (class "Default")
      (node (ref "U1") (pin "26") (pinfunction "PB0_26") (pintype "bidirectional"))
    )
    (net (code "75") (name "unconnected-(U1-PB1-Pad27)") (class "Default")
      (node (ref "U1") (pin "27") (pinfunction "PB1_27") (pintype "bidirectional"))
    )
    (net (code "76") (name "unconnected-(U1-PB5-Pad57)") (class "Default")
      (node (ref "U1") (pin "57") (pinfunction "PB5_57") (pintype "bidirectional"))
    )
    (net (code "77") (name "unconnected-(U1-PB8-Pad61)") (class "Default")
      (node (ref "U1") (pin "61") (pinfunction "PB8_61") (pintype "bidirectional"))
    )
    (net (code "78") (name "unconnected-(U1-PB9-Pad62)") (class "Default")
      (node (ref "U1") (pin "62") (pinfunction "PB9_62") (pintype "bidirectional"))
    )
    (net (code "79") (name "unconnected-(U1-PC0-Pad8)") (class "Default")
      (node (ref "U1") (pin "8") (pinfunction "PC0_8") (pintype "bidirectional"))
    )
    (net (code "80") (name "unconnected-(U1-PC3-Pad11)") (class "Default")
      (node (ref "U1") (pin "11") (pinfunction "PC3_11") (pintype "bidirectional"))
    )
    (net (code "81") (name "unconnected-(U1-PC4-Pad24)") (class "Default")
      (node (ref "U1") (pin "24") (pinfunction "PC4_24") (pintype "bidirectional"))
    )
    (net (code "82") (name "unconnected-(U1-PC5-Pad25)") (class "Default")
      (node (ref "U1") (pin "25") (pinfunction "PC5_25") (pintype "bidirectional"))
    )
    (net (code "83") (name "unconnected-(U1-PC6-Pad37)") (class "Default")
      (node (ref "U1") (pin "37") (pinfunction "PC6_37") (pintype "bidirectional"))
    )
    (net (code "84") (name "unconnected-(U1-PC7-Pad38)") (class "Default")
      (node (ref "U1") (pin "38") (pinfunction "PC7_38") (pintype "bidirectional"))
    )
    (net (code "85") (name "unconnected-(U1-PC13-Pad2)") (class "Default")
      (node (ref "U1") (pin "2") (pinfunction "PC13_2") (pintype "bidirectional"))
    )
    (net (code "86") (name "unconnected-(U1-PC14-Pad3)") (class "Default")
      (node (ref "U1") (pin "3") (pinfunction "PC14_3") (pintype "bidirectional"))
    )
    (net (code "87") (name "unconnected-(U1-PC15-Pad4)") (class "Default")
      (node (ref "U1") (pin "4") (pinfunction "PC15_4") (pintype "bidirectional"))
    )
    (net (code "88") (name "unconnected-(U1-WKUP{slash}PA0-Pad14)") (class "Default")
      (node (ref "U1") (pin "14") (pinfunction "WKUP/PA0_14") (pintype "bidirectional"))
    )
  )
)
